# BACKPMAN30_CPU.net
KiCad netlist of a schematic drawn in Altium Designer
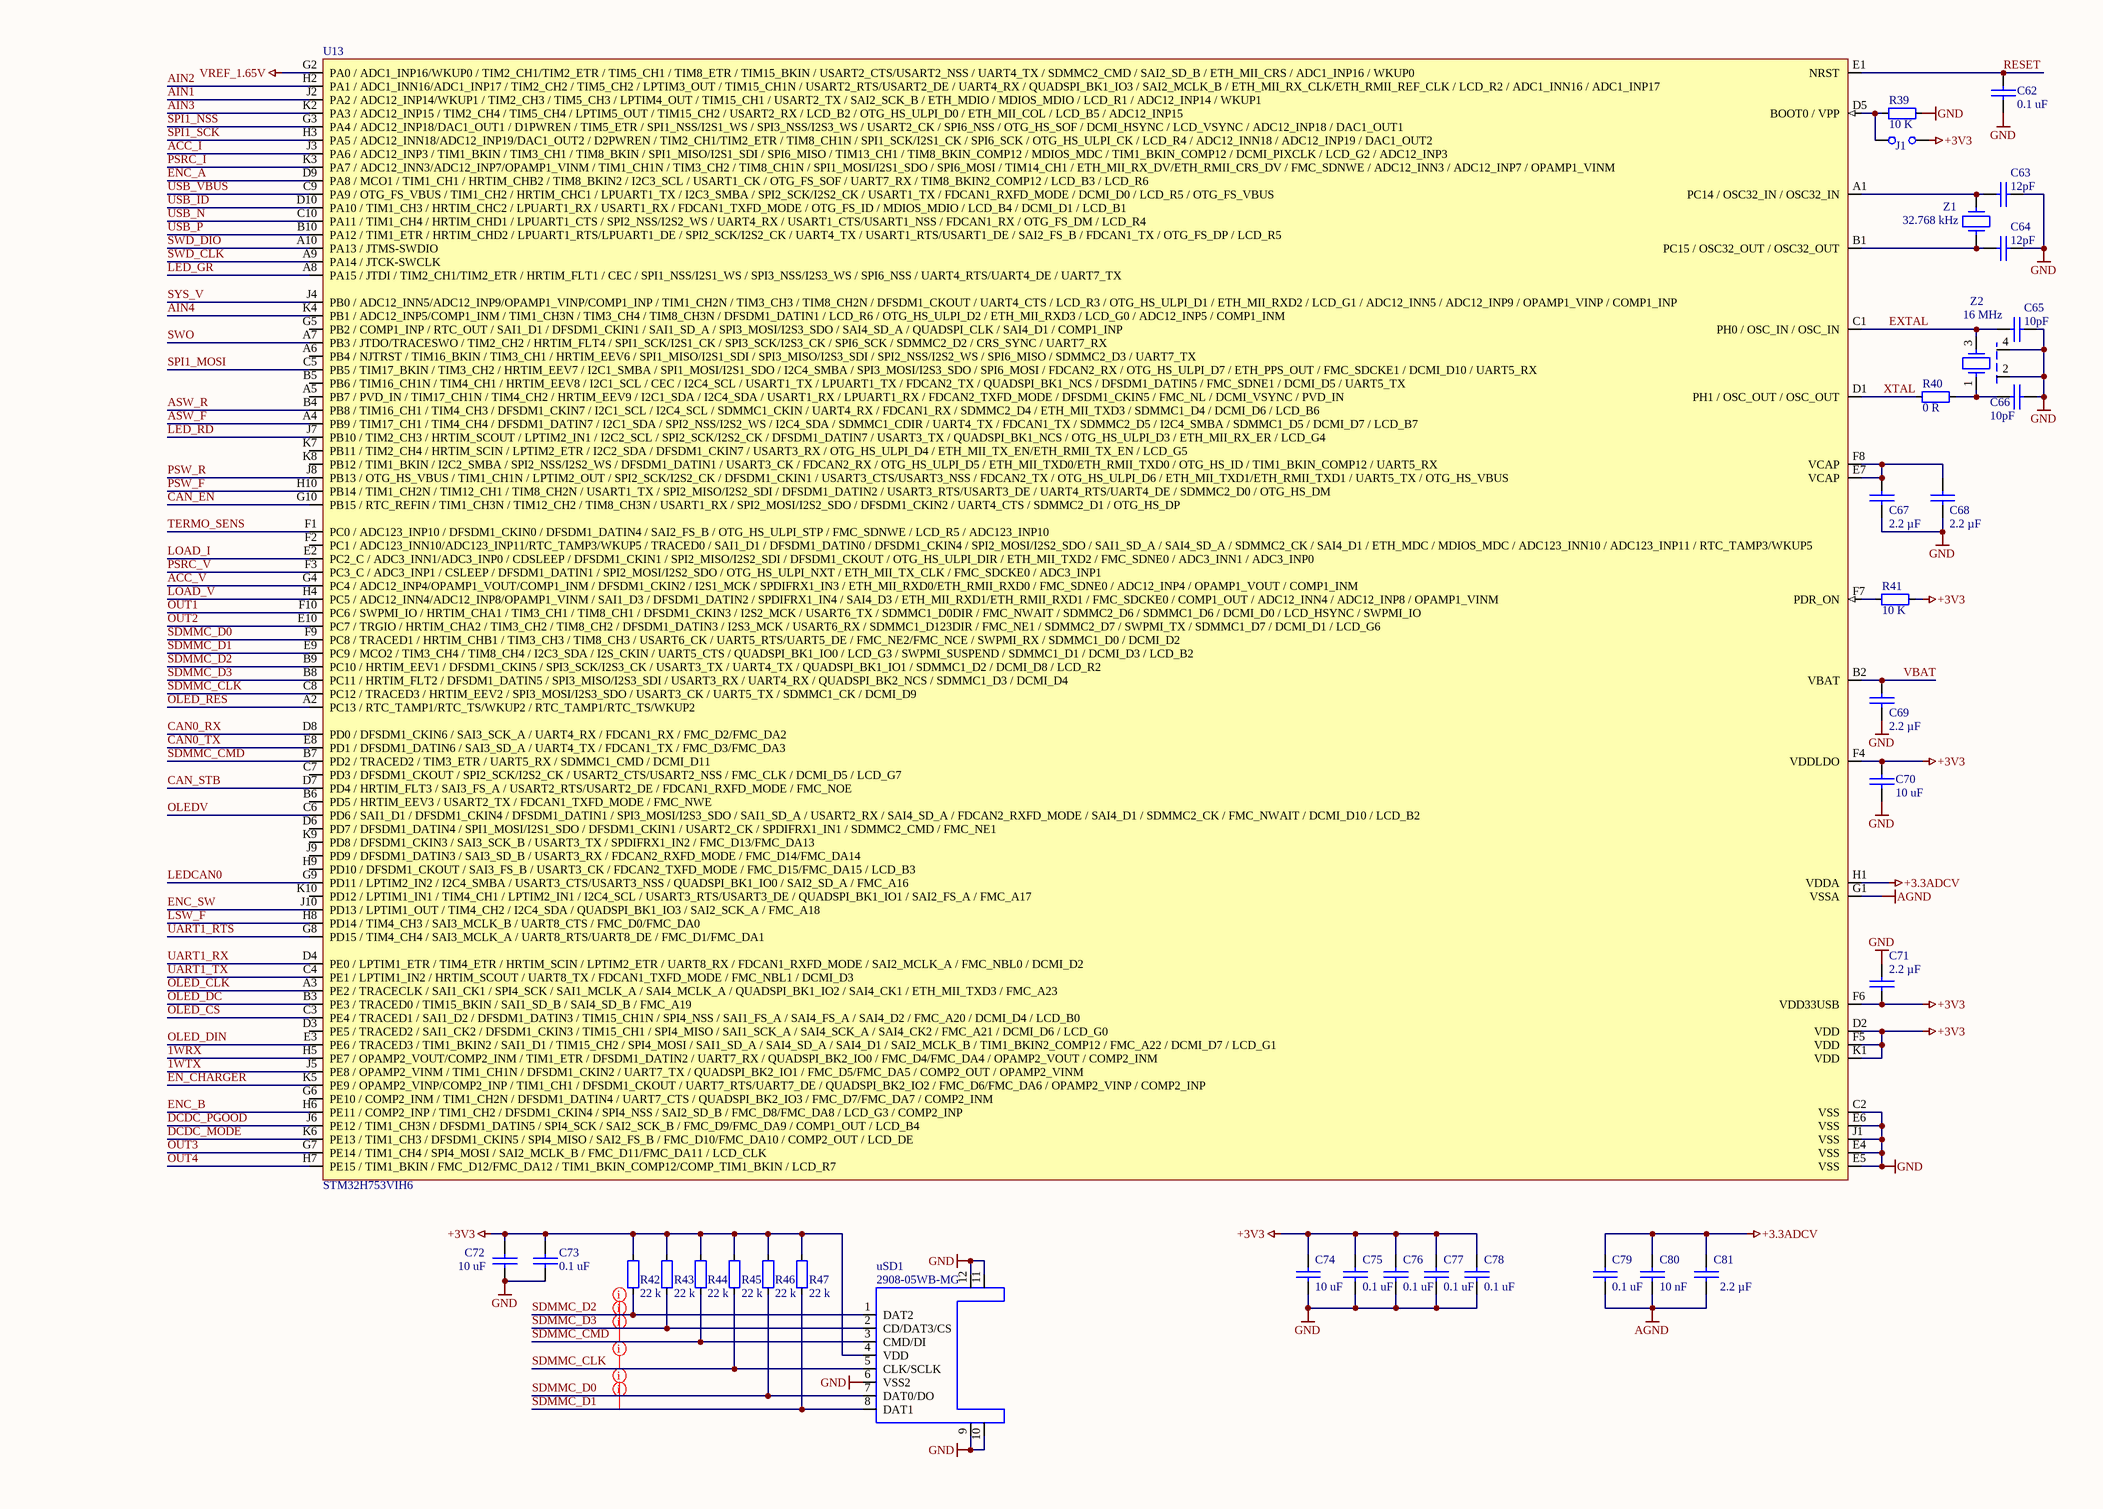
[diagram p0: BACKPMAN30_CPU.SchDoc]

(export (version "E")
  (design (tool "Eeschema 10.0.6"))
  (components
    (comp (ref "C62")
      (value "0.1 uF")
      (footprint "1608[0603]")
      (description "0.1 µF ±10% 50V Ceramic Capacitor X7R 0603 (1608 Metric), -55°C ~ 125°C")
      (fields
        (field (name "TOLERANCE") "+-10%")
        (field (name "MANUFACTURER") "Walsin Technology Corporation")
      )
      (libsource (lib "ea_Capacitors_0603") (part "0603B104K500CT"))
    )
    (comp (ref "C63")
      (value "12pF")
      (footprint "0402 CAP")
      (description "12pF, ±2%, 50V, C0G, NP0, 0402 (1005 Metric), -55°C ~ 125°C, -, General Purpose")
      (fields
        (field (name "PART NUMBER") "0402N120G500CT")
        (field (name "MANUFACTURER") "Walsin Technology Corporation")
      )
      (libsource (lib "ea_PassivComps") (part "Capacitor"))
    )
    (comp (ref "C64")
      (value "12pF")
      (footprint "0402 CAP")
      (description "12pF, ±2%, 50V, C0G, NP0, 0402 (1005 Metric), -55°C ~ 125°C, -, General Purpose")
      (fields
        (field (name "PART NUMBER") "0402N120G500CT")
        (field (name "MANUFACTURER") "Walsin Technology Corporation")
      )
      (libsource (lib "ea_PassivComps") (part "Capacitor"))
    )
    (comp (ref "C65")
      (value "10pF")
      (footprint "0402 CAP")
      (description "10pF, ±1%, 50V, C0G, NP0, 0402 (1005 Metric), -55°C ~ 125°C, -, Automotive")
      (fields
        (field (name "PART NUMBER") "GCM1555C1H100FA16D")
        (field (name "MANUFACTURER") "Murata Electronics North America")
      )
      (libsource (lib "ea_PassivComps") (part "Capacitor"))
    )
    (comp (ref "C66")
      (value "10pF")
      (footprint "0402 CAP")
      (description "10pF, ±1%, 50V, C0G, NP0, 0402 (1005 Metric), -55°C ~ 125°C, -, Automotive")
      (fields
        (field (name "PART NUMBER") "GCM1555C1H100FA16D")
        (field (name "MANUFACTURER") "Murata Electronics North America")
      )
      (libsource (lib "ea_PassivComps") (part "Capacitor"))
    )
    (comp (ref "C67")
      (value "2.2 µF")
      (footprint "1608[0603]")
      (description "2.2 µF ±10% 16V Ceramic Capacitor X5R 0603 (1608 Metric), -55°C ~ 85°C")
      (fields (field (name "MANUFACTURER") "TDK Corporation") (field (name "PARTNUM") "445-5157-1-ND"))
      (libsource (lib "ea_Capacitors_0603") (part "C1608X5R1C225K080AB"))
    )
    (comp (ref "C68")
      (value "2.2 µF")
      (footprint "1608[0603]")
      (description "2.2 µF ±10% 16V Ceramic Capacitor X5R 0603 (1608 Metric), -55°C ~ 85°C")
      (fields (field (name "MANUFACTURER") "TDK Corporation") (field (name "PARTNUM") "445-5157-1-ND"))
      (libsource (lib "ea_Capacitors_0603") (part "C1608X5R1C225K080AB"))
    )
    (comp (ref "C69")
      (value "2.2 µF")
      (footprint "1608[0603]")
      (description "2.2 µF ±10% 16V Ceramic Capacitor X5R 0603 (1608 Metric), -55°C ~ 85°C")
      (fields (field (name "MANUFACTURER") "TDK Corporation") (field (name "PARTNUM") "445-5157-1-ND"))
      (libsource (lib "ea_Capacitors_0603") (part "C1608X5R1C225K080AB"))
    )
    (comp (ref "C70")
      (value "10 uF")
      (footprint "2012[0805]")
      (description "10 µF ±10%, 25V, Ceramic Capacitor X5R 0805 (2012 Metric),  -55°C ~ 85°C")
      (fields (field (name "MANUFACTURER") "Murata Electronics") (field (name "TOLERANCE") "±10%"))
      (libsource (lib "ea_Capacitors_0805") (part "GRM21BR61E106KA73L"))
    )
    (comp (ref "C71")
      (value "2.2 µF")
      (footprint "1608[0603]")
      (description "2.2 µF ±10% 16V Ceramic Capacitor X5R 0603 (1608 Metric), -55°C ~ 85°C")
      (fields (field (name "MANUFACTURER") "TDK Corporation") (field (name "PARTNUM") "445-5157-1-ND"))
      (libsource (lib "ea_Capacitors_0603") (part "C1608X5R1C225K080AB"))
    )
    (comp (ref "C72")
      (value "10 uF")
      (footprint "2012[0805]")
      (description "10 µF ±10%, 25V, Ceramic Capacitor X5R 0805 (2012 Metric),  -55°C ~ 85°C")
      (fields (field (name "MANUFACTURER") "Murata Electronics") (field (name "PARTNUM") "490-5523-1-ND"))
      (libsource (lib "ea_Capacitors_0805") (part "GRM21BR61E106KA73L"))
    )
    (comp (ref "C73")
      (value "0.1 uF")
      (footprint "1608[0603]")
      (description "0.1 µF ±10% 50V Ceramic Capacitor X7R 0603 (1608 Metric), -55°C ~ 125°C")
      (fields
        (field (name "MANUFACTURER") "Walsin Technology Corporation")
        (field (name "PARTNUM") "1292-1643-1-ND")
      )
      (libsource (lib "ea_Capacitors_0603") (part "0603B104K500CT"))
    )
    (comp (ref "C74")
      (value "10 uF")
      (footprint "2012[0805]")
      (description "10 µF ±10%, 25V, Ceramic Capacitor X5R 0805 (2012 Metric),  -55°C ~ 85°C")
      (fields (field (name "MANUFACTURER") "Murata Electronics") (field (name "TOLERANCE") "±10%"))
      (libsource (lib "ea_Capacitors_0805") (part "GRM21BR61E106KA73L"))
    )
    (comp (ref "C75")
      (value "0.1 uF")
      (footprint "1608[0603]")
      (description "0.1 µF ±10% 50V Ceramic Capacitor X7R 0603 (1608 Metric), -55°C ~ 125°C")
      (fields
        (field (name "TOLERANCE") "+-10%")
        (field (name "MANUFACTURER") "Walsin Technology Corporation")
      )
      (libsource (lib "ea_Capacitors_0603") (part "0603B104K500CT"))
    )
    (comp (ref "C76")
      (value "0.1 uF")
      (footprint "1608[0603]")
      (description "0.1 µF ±10% 50V Ceramic Capacitor X7R 0603 (1608 Metric), -55°C ~ 125°C")
      (fields
        (field (name "TOLERANCE") "+-10%")
        (field (name "MANUFACTURER") "Walsin Technology Corporation")
      )
      (libsource (lib "ea_Capacitors_0603") (part "0603B104K500CT"))
    )
    (comp (ref "C77")
      (value "0.1 uF")
      (footprint "1608[0603]")
      (description "0.1 µF ±10% 50V Ceramic Capacitor X7R 0603 (1608 Metric), -55°C ~ 125°C")
      (fields
        (field (name "TOLERANCE") "+-10%")
        (field (name "MANUFACTURER") "Walsin Technology Corporation")
      )
      (libsource (lib "ea_Capacitors_0603") (part "0603B104K500CT"))
    )
    (comp (ref "C78")
      (value "0.1 uF")
      (footprint "1608[0603]")
      (description "0.1 µF ±10% 50V Ceramic Capacitor X7R 0603 (1608 Metric), -55°C ~ 125°C")
      (fields
        (field (name "TOLERANCE") "+-10%")
        (field (name "MANUFACTURER") "Walsin Technology Corporation")
      )
      (libsource (lib "ea_Capacitors_0603") (part "0603B104K500CT"))
    )
    (comp (ref "C79")
      (value "0.1 uF")
      (footprint "1608[0603]")
      (description "0.1 µF ±10% 50V Ceramic Capacitor X7R 0603 (1608 Metric), -55°C ~ 125°C")
      (fields
        (field (name "TOLERANCE") "+-10%")
        (field (name "MANUFACTURER") "Walsin Technology Corporation")
      )
      (libsource (lib "ea_Capacitors_0603") (part "0603B104K500CT"))
    )
    (comp (ref "C80")
      (value "10 nF")
      (footprint "1608[0603]")
      (description "10 nF, ±20%, 50V,  Ceramic Capacitor X7R 0603 (1608 Metric), -55°C ~ 125°C")
      (fields (field (name "TOLERANCE") "+-10%") (field (name "MANUFACTURER") "CAL-CHIP ELECTRONICS, INC."))
      (libsource (lib "ea_Capacitors_0603") (part "GMC10X7R103M50NT"))
    )
    (comp (ref "C81")
      (value "2.2 µF")
      (footprint "1608[0603]")
      (description "2.2 µF ±10% 16V Ceramic Capacitor X5R 0603 (1608 Metric), -55°C ~ 85°C")
      (fields (field (name "MANUFACTURER") "TDK Corporation") (field (name "PARTNUM") "445-5157-1-ND"))
      (libsource (lib "ea_Capacitors_0603") (part "C1608X5R1C225K080AB"))
    )
    (comp (ref "J1")
      (value "PH1-02-TA-HT")
      (footprint "HDR1X2V")
      (description "Connector Header Through Hole 2 position 0.100\" (2.54mm), Contact Length - Mating 6 mm")
      (fields (field (name "MANUFACTURER") "Adam Tech") (field (name "PARTNUM") "2057-PH1-02-UA-ND"))
      (libsource (lib "ea_Commutation") (part "PH1-02-UA"))
    )
    (comp (ref "R39")
      (value "10 K")
      (footprint "0603")
      (fields
        (field (name "MANUFACTURER") "Stackpole Electronics Inc")
        (field (name "TOLERANCE") "1%")
        (field (name "PARTNUM") "RMCF0603FT10K0CT-ND")
      )
      (libsource (lib "ea_Resistors_0603") (part "RMCF0603FT10K0"))
    )
    (comp (ref "R40")
      (value "0 R")
      (footprint "0603")
      (description "0 Ohms Jumper 0.1W, 1/10W Chip Resistor 0603 (1608 Metric) - Thick Film, -55°C ~ 155°C")
      (fields (field (name "MANUFACTURER") "Venkel") (field (name "VOLTAGE") "75 V"))
      (libsource (lib "ea_Resistors_0603") (part "CR0603-10W-000T"))
    )
    (comp (ref "R41")
      (value "10 K")
      (footprint "0603")
      (fields
        (field (name "MANUFACTURER") "Stackpole Electronics Inc")
        (field (name "TOLERANCE") "1%")
        (field (name "PARTNUM") "RMCF0603FT10K0CT-ND")
      )
      (libsource (lib "ea_Resistors_0603") (part "RMCF0603FT10K0"))
    )
    (comp (ref "R42")
      (value "22 k")
      (footprint "0402")
      (fields
        (field (name "MANUFACTURER") "Stackpole Electronics Inc")
        (field (name "TOLERANCE") "±1%")
        (field (name "VOLTAGE") "75V")
      )
      (libsource (lib "ea_PassivComps") (part "Resistor"))
    )
    (comp (ref "R43")
      (value "22 k")
      (footprint "0402")
      (fields
        (field (name "MANUFACTURER") "Stackpole Electronics Inc")
        (field (name "TOLERANCE") "±1%")
        (field (name "VOLTAGE") "75V")
      )
      (libsource (lib "ea_PassivComps") (part "Resistor"))
    )
    (comp (ref "R44")
      (value "22 k")
      (footprint "0402")
      (fields
        (field (name "MANUFACTURER") "Stackpole Electronics Inc")
        (field (name "TOLERANCE") "±1%")
        (field (name "VOLTAGE") "75V")
      )
      (libsource (lib "ea_PassivComps") (part "Resistor"))
    )
    (comp (ref "R45")
      (value "22 k")
      (footprint "0402")
      (fields
        (field (name "MANUFACTURER") "Stackpole Electronics Inc")
        (field (name "TOLERANCE") "±1%")
        (field (name "VOLTAGE") "75V")
      )
      (libsource (lib "ea_PassivComps") (part "Resistor"))
    )
    (comp (ref "R46")
      (value "22 k")
      (footprint "0402")
      (fields
        (field (name "MANUFACTURER") "Stackpole Electronics Inc")
        (field (name "TOLERANCE") "±1%")
        (field (name "VOLTAGE") "75V")
      )
      (libsource (lib "ea_PassivComps") (part "Resistor"))
    )
    (comp (ref "R47")
      (value "22 k")
      (footprint "0402")
      (fields
        (field (name "MANUFACTURER") "Stackpole Electronics Inc")
        (field (name "TOLERANCE") "±1%")
        (field (name "VOLTAGE") "75V")
      )
      (libsource (lib "ea_PassivComps") (part "Resistor"))
    )
    (comp (ref "U13")
      (value "STM32H753VIH6")
      (footprint "TFBGA100")
      (description "Cortex-M7, 480MHz 2MB FLASH, 1MB RAM, 100-TFBGA (8x8)")
      (fields (field (name "MANUFACTURER") "STMicroelectronics") (field (name "PARTNUM") "STM32H753VIH6-ND"))
      (libsource (lib "ea_IC_CPU") (part "STM32H753VIH6"))
    )
    (comp (ref "uSD1")
      (value "2908-05WB-MG")
      (footprint "2908-05WB-MG")
      (description "microSD cadr holder")
      (fields (field (name "MANUFACTURER") "3M"))
      (libsource (lib "ea_CARD_holders") (part "2908-05WB-MG"))
    )
    (comp (ref "Z1")
      (value "32.768 kHz")
      (footprint "ABS7")
      (description "32.768 kHz, 12.5 pF, 70 kOhm, ±20ppm, 3.2 x 1.5 mm, -40°C ~ 85°C")
      (fields (field (name "MANUFACTURER") "Abracon Corporation") (field (name "PARTNUM") "535-9542-1-ND"))
      (libsource (lib "ea_OSC_CLK_GEN") (part "ABS07-32.768KHZ-T"))
    )
    (comp (ref "Z2")
      (value "16 MHz")
      (footprint "4-SMD 2.00mm x 1.60mm")
      (description "16 MHz, 9 pF, ±10ppm, 2.00mm x 1.60mm, -20°C ~ 70°C")
      (fields (field (name "MANUFACTURER") "Abracon LLC") (field (name "PARTNUM") "535-13598-1-ND"))
      (libsource (lib "ea_OSC_CLK_GEN") (part "ABM11-16.000MHZ-9-B1U-T"))
    )
  )
  (nets
    (net (code "1") (name "+3.3ADCV") (class "Default")
      (node (ref "C79") (pin "2") (pinfunction "2_2") (pintype "passive"))
      (node (ref "C80") (pin "1") (pinfunction "1_1") (pintype "passive"))
      (node (ref "C81") (pin "1") (pinfunction "1_1") (pintype "passive"))
      (node (ref "U13") (pin "H1") (pinfunction "VDDA_H1") (pintype "power_in"))
    )
    (net (code "2") (name "+3V3") (class "Default")
      (node (ref "C70") (pin "2") (pinfunction "2_2") (pintype "passive"))
      (node (ref "C71") (pin "2") (pinfunction "2_2") (pintype "passive"))
      (node (ref "C72") (pin "2") (pinfunction "2_2") (pintype "passive"))
      (node (ref "C73") (pin "2") (pinfunction "2_2") (pintype "passive"))
      (node (ref "C74") (pin "2") (pinfunction "2_2") (pintype "passive"))
      (node (ref "C75") (pin "2") (pinfunction "2_2") (pintype "passive"))
      (node (ref "C76") (pin "2") (pinfunction "2_2") (pintype "passive"))
      (node (ref "C77") (pin "2") (pinfunction "2_2") (pintype "passive"))
      (node (ref "C78") (pin "2") (pinfunction "2_2") (pintype "passive"))
      (node (ref "J1") (pin "2") (pinfunction "2_2") (pintype "passive"))
      (node (ref "R41") (pin "1") (pinfunction "1_1") (pintype "passive"))
      (node (ref "R42") (pin "2") (pinfunction "2_2") (pintype "passive"))
      (node (ref "R43") (pin "2") (pinfunction "2_2") (pintype "passive"))
      (node (ref "R44") (pin "2") (pinfunction "2_2") (pintype "passive"))
      (node (ref "R45") (pin "2") (pinfunction "2_2") (pintype "passive"))
      (node (ref "R46") (pin "2") (pinfunction "2_2") (pintype "passive"))
      (node (ref "R47") (pin "2") (pinfunction "2_2") (pintype "passive"))
      (node (ref "U13") (pin "D2") (pinfunction "VDD_D2") (pintype "power_in"))
      (node (ref "U13") (pin "F4") (pinfunction "VDDLDO_F4") (pintype "power_in"))
      (node (ref "U13") (pin "F5") (pinfunction "VDD_F5") (pintype "power_in"))
      (node (ref "U13") (pin "F6") (pinfunction "VDD33USB_F6") (pintype "power_in"))
      (node (ref "U13") (pin "K1") (pinfunction "VDD_K1") (pintype "power_in"))
      (node (ref "uSD1") (pin "4") (pinfunction "VDD_4") (pintype "passive"))
    )
    (net (code "3") (name "/1WRX") (class "Default")
      (node (ref "U13") (pin "H5") (pinfunction "PE7_/_OPAMP2_VOUT/COMP2_INM_/_TIM1_ETR_/_DFSDM1_DATIN2_/_UART7_RX_/_QUADSPI_BK2_IO0_/_FMC_D4/FMC_DA4_/_OPAMP2_VOUT_/_COMP2_INM_H5") (pintype "bidirectional"))
    )
    (net (code "4") (name "/1WTX") (class "Default")
      (node (ref "U13") (pin "J5") (pinfunction "PE8_/_OPAMP2_VINM_/_TIM1_CH1N_/_DFSDM1_CKIN2_/_UART7_TX_/_QUADSPI_BK2_IO1_/_FMC_D5/FMC_DA5_/_COMP2_OUT_/_OPAMP2_VINM_J5") (pintype "bidirectional"))
    )
    (net (code "5") (name "/ACC_I") (class "Default")
      (node (ref "U13") (pin "J3") (pinfunction "PA6_/_ADC12_INP3_/_TIM1_BKIN_/_TIM3_CH1_/_TIM8_BKIN_/_SPI1_MISO/I2S1_SDI_/_SPI6_MISO_/_TIM13_CH1_/_TIM8_BKIN_COMP12_/_MDIOS_MDC_/_TIM1_BKIN_COMP12_/_DCMI_PIXCLK_/_LCD_G2_/_ADC12_INP3_J3") (pintype "bidirectional"))
    )
    (net (code "6") (name "/ACC_V") (class "Default")
      (node (ref "U13") (pin "G4") (pinfunction "PC4_/_ADC12_INP4/OPAMP1_VOUT/COMP1_INM_/_DFSDM1_CKIN2_/_I2S1_MCK_/_SPDIFRX1_IN3_/_ETH_MII_RXD0/ETH_RMII_RXD0_/_FMC_SDNE0_/_ADC12_INP4_/_OPAMP1_VOUT_/_COMP1_INM_G4") (pintype "bidirectional"))
    )
    (net (code "7") (name "/AIN1") (class "Default")
      (node (ref "U13") (pin "J2") (pinfunction "PA2_/_ADC12_INP14/WKUP1_/_TIM2_CH3_/_TIM5_CH3_/_LPTIM4_OUT_/_TIM15_CH1_/_USART2_TX_/_SAI2_SCK_B_/_ETH_MDIO_/_MDIOS_MDIO_/_LCD_R1_/_ADC12_INP14_/_WKUP1_J2") (pintype "bidirectional"))
    )
    (net (code "8") (name "/AIN2") (class "Default")
      (node (ref "U13") (pin "H2") (pinfunction "PA1_/_ADC1_INN16/ADC1_INP17_/_TIM2_CH2_/_TIM5_CH2_/_LPTIM3_OUT_/_TIM15_CH1N_/_USART2_RTS/USART2_DE_/_UART4_RX_/_QUADSPI_BK1_IO3_/_SAI2_MCLK_B_/_ETH_MII_RX_CLK/ETH_RMII_REF_CLK_/_LCD_R2_/_ADC1_INN16_/_ADC1_INP17_H2") (pintype "bidirectional"))
    )
    (net (code "9") (name "/AIN3") (class "Default")
      (node (ref "U13") (pin "K2") (pinfunction "PA3_/_ADC12_INP15_/_TIM2_CH4_/_TIM5_CH4_/_LPTIM5_OUT_/_TIM15_CH2_/_USART2_RX_/_LCD_B2_/_OTG_HS_ULPI_D0_/_ETH_MII_COL_/_LCD_B5_/_ADC12_INP15_K2") (pintype "bidirectional"))
    )
    (net (code "10") (name "/AIN4") (class "Default")
      (node (ref "U13") (pin "K4") (pinfunction "PB1_/_ADC12_INP5/COMP1_INM_/_TIM1_CH3N_/_TIM3_CH4_/_TIM8_CH3N_/_DFSDM1_DATIN1_/_LCD_R6_/_OTG_HS_ULPI_D2_/_ETH_MII_RXD3_/_LCD_G0_/_ADC12_INP5_/_COMP1_INM_K4") (pintype "bidirectional"))
    )
    (net (code "11") (name "/ASW_F") (class "Default")
      (node (ref "U13") (pin "A4") (pinfunction "PB9_/_TIM17_CH1_/_TIM4_CH4_/_DFSDM1_DATIN7_/_I2C1_SDA_/_SPI2_NSS/I2S2_WS_/_I2C4_SDA_/_SDMMC1_CDIR_/_UART4_TX_/_FDCAN1_TX_/_SDMMC2_D5_/_I2C4_SMBA_/_SDMMC1_D5_/_DCMI_D7_/_LCD_B7_A4") (pintype "bidirectional"))
    )
    (net (code "12") (name "/ASW_R") (class "Default")
      (node (ref "U13") (pin "B4") (pinfunction "PB8_/_TIM16_CH1_/_TIM4_CH3_/_DFSDM1_CKIN7_/_I2C1_SCL_/_I2C4_SCL_/_SDMMC1_CKIN_/_UART4_RX_/_FDCAN1_RX_/_SDMMC2_D4_/_ETH_MII_TXD3_/_SDMMC1_D4_/_DCMI_D6_/_LCD_B6_B4") (pintype "bidirectional"))
    )
    (net (code "13") (name "/CAN0_RX") (class "Default")
      (node (ref "U13") (pin "D8") (pinfunction "PD0_/_DFSDM1_CKIN6_/_SAI3_SCK_A_/_UART4_RX_/_FDCAN1_RX_/_FMC_D2/FMC_DA2_D8") (pintype "bidirectional"))
    )
    (net (code "14") (name "/CAN0_TX") (class "Default")
      (node (ref "U13") (pin "E8") (pinfunction "PD1_/_DFSDM1_DATIN6_/_SAI3_SD_A_/_UART4_TX_/_FDCAN1_TX_/_FMC_D3/FMC_DA3_E8") (pintype "bidirectional"))
    )
    (net (code "15") (name "/CAN_EN") (class "Default")
      (node (ref "U13") (pin "G10") (pinfunction "PB15_/_RTC_REFIN_/_TIM1_CH3N_/_TIM12_CH2_/_TIM8_CH3N_/_USART1_RX_/_SPI2_MOSI/I2S2_SDO_/_DFSDM1_CKIN2_/_UART4_CTS_/_SDMMC2_D1_/_OTG_HS_DP_G10") (pintype "bidirectional"))
    )
    (net (code "16") (name "/CAN_STB") (class "Default")
      (node (ref "U13") (pin "D7") (pinfunction "PD4_/_HRTIM_FLT3_/_SAI3_FS_A_/_USART2_RTS/USART2_DE_/_FDCAN1_RXFD_MODE_/_FMC_NOE_D7") (pintype "bidirectional"))
    )
    (net (code "17") (name "/DCDC_MODE") (class "Default")
      (node (ref "U13") (pin "K6") (pinfunction "PE13_/_TIM1_CH3_/_DFSDM1_CKIN5_/_SPI4_MISO_/_SAI2_FS_B_/_FMC_D10/FMC_DA10_/_COMP2_OUT_/_LCD_DE_K6") (pintype "bidirectional"))
    )
    (net (code "18") (name "/DCDC_PGOOD") (class "Default")
      (node (ref "U13") (pin "J6") (pinfunction "PE12_/_TIM1_CH3N_/_DFSDM1_DATIN5_/_SPI4_SCK_/_SAI2_SCK_B_/_FMC_D9/FMC_DA9_/_COMP1_OUT_/_LCD_B4_J6") (pintype "bidirectional"))
    )
    (net (code "19") (name "/ENC_A") (class "Default")
      (node (ref "U13") (pin "D9") (pinfunction "PA8_/_MCO1_/_TIM1_CH1_/_HRTIM_CHB2_/_TIM8_BKIN2_/_I2C3_SCL_/_USART1_CK_/_OTG_FS_SOF_/_UART7_RX_/_TIM8_BKIN2_COMP12_/_LCD_B3_/_LCD_R6_D9") (pintype "bidirectional"))
    )
    (net (code "20") (name "/ENC_B") (class "Default")
      (node (ref "U13") (pin "H6") (pinfunction "PE11_/_COMP2_INP_/_TIM1_CH2_/_DFSDM1_CKIN4_/_SPI4_NSS_/_SAI2_SD_B_/_FMC_D8/FMC_DA8_/_LCD_G3_/_COMP2_INP_H6") (pintype "bidirectional"))
    )
    (net (code "21") (name "/ENC_SW") (class "Default")
      (node (ref "U13") (pin "J10") (pinfunction "PD13_/_LPTIM1_OUT_/_TIM4_CH2_/_I2C4_SDA_/_QUADSPI_BK1_IO3_/_SAI2_SCK_A_/_FMC_A18_J10") (pintype "bidirectional"))
    )
    (net (code "22") (name "/EN_CHARGER") (class "Default")
      (node (ref "U13") (pin "K5") (pinfunction "PE9_/_OPAMP2_VINP/COMP2_INP_/_TIM1_CH1_/_DFSDM1_CKOUT_/_UART7_RTS/UART7_DE_/_QUADSPI_BK2_IO2_/_FMC_D6/FMC_DA6_/_OPAMP2_VINP_/_COMP2_INP_K5") (pintype "bidirectional"))
    )
    (net (code "23") (name "/EXTAL") (class "Default")
      (node (ref "C65") (pin "1") (pinfunction "1_1") (pintype "passive"))
      (node (ref "U13") (pin "C1") (pinfunction "PH0_/_OSC_IN_/_OSC_IN_C1") (pintype "bidirectional"))
      (node (ref "Z2") (pin "3") (pinfunction "3_3") (pintype "passive"))
    )
    (net (code "24") (name "/LEDCAN0") (class "Default")
      (node (ref "U13") (pin "G9") (pinfunction "PD11_/_LPTIM2_IN2_/_I2C4_SMBA_/_USART3_CTS/USART3_NSS_/_QUADSPI_BK1_IO0_/_SAI2_SD_A_/_FMC_A16_G9") (pintype "bidirectional"))
    )
    (net (code "25") (name "/LED_GR") (class "Default")
      (node (ref "U13") (pin "A8") (pinfunction "PA15_/_JTDI_/_TIM2_CH1/TIM2_ETR_/_HRTIM_FLT1_/_CEC_/_SPI1_NSS/I2S1_WS_/_SPI3_NSS/I2S3_WS_/_SPI6_NSS_/_UART4_RTS/UART4_DE_/_UART7_TX_A8") (pintype "bidirectional"))
    )
    (net (code "26") (name "/LED_RD") (class "Default")
      (node (ref "U13") (pin "J7") (pinfunction "PB10_/_TIM2_CH3_/_HRTIM_SCOUT_/_LPTIM2_IN1_/_I2C2_SCL_/_SPI2_SCK/I2S2_CK_/_DFSDM1_DATIN7_/_USART3_TX_/_QUADSPI_BK1_NCS_/_OTG_HS_ULPI_D3_/_ETH_MII_RX_ER_/_LCD_G4_J7") (pintype "bidirectional"))
    )
    (net (code "27") (name "/LOAD_I") (class "Default")
      (node (ref "U13") (pin "E2") (pinfunction "PC2_C_/_ADC3_INN1/ADC3_INP0_/_CDSLEEP_/_DFSDM1_CKIN1_/_SPI2_MISO/I2S2_SDI_/_DFSDM1_CKOUT_/_OTG_HS_ULPI_DIR_/_ETH_MII_TXD2_/_FMC_SDNE0_/_ADC3_INN1_/_ADC3_INP0_E2") (pintype "bidirectional"))
    )
    (net (code "28") (name "/LOAD_V") (class "Default")
      (node (ref "U13") (pin "H4") (pinfunction "PC5_/_ADC12_INN4/ADC12_INP8/OPAMP1_VINM_/_SAI1_D3_/_DFSDM1_DATIN2_/_SPDIFRX1_IN4_/_SAI4_D3_/_ETH_MII_RXD1/ETH_RMII_RXD1_/_FMC_SDCKE0_/_COMP1_OUT_/_ADC12_INN4_/_ADC12_INP8_/_OPAMP1_VINM_H4") (pintype "bidirectional"))
    )
    (net (code "29") (name "/LSW_F") (class "Default")
      (node (ref "U13") (pin "H8") (pinfunction "PD14_/_TIM4_CH3_/_SAI3_MCLK_B_/_UART8_CTS_/_FMC_D0/FMC_DA0_H8") (pintype "bidirectional"))
    )
    (net (code "30") (name "/OLEDV") (class "Default")
      (node (ref "U13") (pin "C6") (pinfunction "PD6_/_SAI1_D1_/_DFSDM1_CKIN4_/_DFSDM1_DATIN1_/_SPI3_MOSI/I2S3_SDO_/_SAI1_SD_A_/_USART2_RX_/_SAI4_SD_A_/_FDCAN2_RXFD_MODE_/_SAI4_D1_/_SDMMC2_CK_/_FMC_NWAIT_/_DCMI_D10_/_LCD_B2_C6") (pintype "bidirectional"))
    )
    (net (code "31") (name "/OLED_CLK") (class "Default")
      (node (ref "U13") (pin "A3") (pinfunction "PE2_/_TRACECLK_/_SAI1_CK1_/_SPI4_SCK_/_SAI1_MCLK_A_/_SAI4_MCLK_A_/_QUADSPI_BK1_IO2_/_SAI4_CK1_/_ETH_MII_TXD3_/_FMC_A23_A3") (pintype "bidirectional"))
    )
    (net (code "32") (name "/OLED_CS") (class "Default")
      (node (ref "U13") (pin "C3") (pinfunction "PE4_/_TRACED1_/_SAI1_D2_/_DFSDM1_DATIN3_/_TIM15_CH1N_/_SPI4_NSS_/_SAI1_FS_A_/_SAI4_FS_A_/_SAI4_D2_/_FMC_A20_/_DCMI_D4_/_LCD_B0_C3") (pintype "bidirectional"))
    )
    (net (code "33") (name "/OLED_DC") (class "Default")
      (node (ref "U13") (pin "B3") (pinfunction "PE3_/_TRACED0_/_TIM15_BKIN_/_SAI1_SD_B_/_SAI4_SD_B_/_FMC_A19_B3") (pintype "bidirectional"))
    )
    (net (code "34") (name "/OLED_DIN") (class "Default")
      (node (ref "U13") (pin "E3") (pinfunction "PE6_/_TRACED3_/_TIM1_BKIN2_/_SAI1_D1_/_TIM15_CH2_/_SPI4_MOSI_/_SAI1_SD_A_/_SAI4_SD_A_/_SAI4_D1_/_SAI2_MCLK_B_/_TIM1_BKIN2_COMP12_/_FMC_A22_/_DCMI_D7_/_LCD_G1_E3") (pintype "bidirectional"))
    )
    (net (code "35") (name "/OLED_RES") (class "Default")
      (node (ref "U13") (pin "A2") (pinfunction "PC13_/_RTC_TAMP1/RTC_TS/WKUP2_/_RTC_TAMP1/RTC_TS/WKUP2_A2") (pintype "bidirectional"))
    )
    (net (code "36") (name "/OUT1") (class "Default")
      (node (ref "U13") (pin "F10") (pinfunction "PC6_/_SWPMI_IO_/_HRTIM_CHA1_/_TIM3_CH1_/_TIM8_CH1_/_DFSDM1_CKIN3_/_I2S2_MCK_/_USART6_TX_/_SDMMC1_D0DIR_/_FMC_NWAIT_/_SDMMC2_D6_/_SDMMC1_D6_/_DCMI_D0_/_LCD_HSYNC_/_SWPMI_IO_F10") (pintype "bidirectional"))
    )
    (net (code "37") (name "/OUT2") (class "Default")
      (node (ref "U13") (pin "E10") (pinfunction "PC7_/_TRGIO_/_HRTIM_CHA2_/_TIM3_CH2_/_TIM8_CH2_/_DFSDM1_DATIN3_/_I2S3_MCK_/_USART6_RX_/_SDMMC1_D123DIR_/_FMC_NE1_/_SDMMC2_D7_/_SWPMI_TX_/_SDMMC1_D7_/_DCMI_D1_/_LCD_G6_E10") (pintype "bidirectional"))
    )
    (net (code "38") (name "/OUT3") (class "Default")
      (node (ref "U13") (pin "G7") (pinfunction "PE14_/_TIM1_CH4_/_SPI4_MOSI_/_SAI2_MCLK_B_/_FMC_D11/FMC_DA11_/_LCD_CLK_G7") (pintype "bidirectional"))
    )
    (net (code "39") (name "/OUT4") (class "Default")
      (node (ref "U13") (pin "H7") (pinfunction "PE15_/_TIM1_BKIN_/_FMC_D12/FMC_DA12_/_TIM1_BKIN_COMP12/COMP_TIM1_BKIN_/_LCD_R7_H7") (pintype "bidirectional"))
    )
    (net (code "40") (name "/PSRC_I") (class "Default")
      (node (ref "U13") (pin "K3") (pinfunction "PA7_/_ADC12_INN3/ADC12_INP7/OPAMP1_VINM_/_TIM1_CH1N_/_TIM3_CH2_/_TIM8_CH1N_/_SPI1_MOSI/I2S1_SDO_/_SPI6_MOSI_/_TIM14_CH1_/_ETH_MII_RX_DV/ETH_RMII_CRS_DV_/_FMC_SDNWE_/_ADC12_INN3_/_ADC12_INP7_/_OPAMP1_VINM_K3") (pintype "bidirectional"))
    )
    (net (code "41") (name "/PSRC_V") (class "Default")
      (node (ref "U13") (pin "F3") (pinfunction "PC3_C_/_ADC3_INP1_/_CSLEEP_/_DFSDM1_DATIN1_/_SPI2_MOSI/I2S2_SDO_/_OTG_HS_ULPI_NXT_/_ETH_MII_TX_CLK_/_FMC_SDCKE0_/_ADC3_INP1_F3") (pintype "bidirectional"))
    )
    (net (code "42") (name "/PSW_F") (class "Default")
      (node (ref "U13") (pin "H10") (pinfunction "PB14_/_TIM1_CH2N_/_TIM12_CH1_/_TIM8_CH2N_/_USART1_TX_/_SPI2_MISO/I2S2_SDI_/_DFSDM1_DATIN2_/_USART3_RTS/USART3_DE_/_UART4_RTS/UART4_DE_/_SDMMC2_D0_/_OTG_HS_DM_H10") (pintype "bidirectional"))
    )
    (net (code "43") (name "/PSW_R") (class "Default")
      (node (ref "U13") (pin "J8") (pinfunction "PB13_/_OTG_HS_VBUS_/_TIM1_CH1N_/_LPTIM2_OUT_/_SPI2_SCK/I2S2_CK_/_DFSDM1_CKIN1_/_USART3_CTS/USART3_NSS_/_FDCAN2_TX_/_OTG_HS_ULPI_D6_/_ETH_MII_TXD1/ETH_RMII_TXD1_/_UART5_TX_/_OTG_HS_VBUS_J8") (pintype "bidirectional"))
    )
    (net (code "44") (name "/RESET") (class "Default")
      (node (ref "C62") (pin "1") (pinfunction "1_1") (pintype "passive"))
      (node (ref "U13") (pin "E1") (pinfunction "NRST_E1") (pintype "bidirectional"))
    )
    (net (code "45") (name "/SDMMC_CLK") (class "Default")
      (node (ref "R45") (pin "1") (pinfunction "1_1") (pintype "passive"))
      (node (ref "U13") (pin "C8") (pinfunction "PC12_/_TRACED3_/_HRTIM_EEV2_/_SPI3_MOSI/I2S3_SDO_/_USART3_CK_/_UART5_TX_/_SDMMC1_CK_/_DCMI_D9_C8") (pintype "bidirectional"))
      (node (ref "uSD1") (pin "5") (pinfunction "CLK/SCLK_5") (pintype "passive"))
    )
    (net (code "46") (name "/SDMMC_CMD") (class "Default")
      (node (ref "R44") (pin "1") (pinfunction "1_1") (pintype "passive"))
      (node (ref "U13") (pin "B7") (pinfunction "PD2_/_TRACED2_/_TIM3_ETR_/_UART5_RX_/_SDMMC1_CMD_/_DCMI_D11_B7") (pintype "bidirectional"))
      (node (ref "uSD1") (pin "3") (pinfunction "CMD/DI_3") (pintype "passive"))
    )
    (net (code "47") (name "/SDMMC_D0") (class "Default")
      (node (ref "R46") (pin "1") (pinfunction "1_1") (pintype "passive"))
      (node (ref "U13") (pin "F9") (pinfunction "PC8_/_TRACED1_/_HRTIM_CHB1_/_TIM3_CH3_/_TIM8_CH3_/_USART6_CK_/_UART5_RTS/UART5_DE_/_FMC_NE2/FMC_NCE_/_SWPMI_RX_/_SDMMC1_D0_/_DCMI_D2_F9") (pintype "bidirectional"))
      (node (ref "uSD1") (pin "7") (pinfunction "DAT0/DO_7") (pintype "passive"))
    )
    (net (code "48") (name "/SDMMC_D1") (class "Default")
      (node (ref "R47") (pin "1") (pinfunction "1_1") (pintype "passive"))
      (node (ref "U13") (pin "E9") (pinfunction "PC9_/_MCO2_/_TIM3_CH4_/_TIM8_CH4_/_I2C3_SDA_/_I2S_CKIN_/_UART5_CTS_/_QUADSPI_BK1_IO0_/_LCD_G3_/_SWPMI_SUSPEND_/_SDMMC1_D1_/_DCMI_D3_/_LCD_B2_E9") (pintype "bidirectional"))
      (node (ref "uSD1") (pin "8") (pinfunction "DAT1_8") (pintype "passive"))
    )
    (net (code "49") (name "/SDMMC_D2") (class "Default")
      (node (ref "R42") (pin "1") (pinfunction "1_1") (pintype "passive"))
      (node (ref "U13") (pin "B9") (pinfunction "PC10_/_HRTIM_EEV1_/_DFSDM1_CKIN5_/_SPI3_SCK/I2S3_CK_/_USART3_TX_/_UART4_TX_/_QUADSPI_BK1_IO1_/_SDMMC1_D2_/_DCMI_D8_/_LCD_R2_B9") (pintype "bidirectional"))
      (node (ref "uSD1") (pin "1") (pinfunction "DAT2_1") (pintype "passive"))
    )
    (net (code "50") (name "/SDMMC_D3") (class "Default")
      (node (ref "R43") (pin "1") (pinfunction "1_1") (pintype "passive"))
      (node (ref "U13") (pin "B8") (pinfunction "PC11_/_HRTIM_FLT2_/_DFSDM1_DATIN5_/_SPI3_MISO/I2S3_SDI_/_USART3_RX_/_UART4_RX_/_QUADSPI_BK2_NCS_/_SDMMC1_D3_/_DCMI_D4_B8") (pintype "bidirectional"))
      (node (ref "uSD1") (pin "2") (pinfunction "CD/DAT3/CS_2") (pintype "passive"))
    )
    (net (code "51") (name "/SPI1_MOSI") (class "Default")
      (node (ref "U13") (pin "C5") (pinfunction "PB5_/_TIM17_BKIN_/_TIM3_CH2_/_HRTIM_EEV7_/_I2C1_SMBA_/_SPI1_MOSI/I2S1_SDO_/_I2C4_SMBA_/_SPI3_MOSI/I2S3_SDO_/_SPI6_MOSI_/_FDCAN2_RX_/_OTG_HS_ULPI_D7_/_ETH_PPS_OUT_/_FMC_SDCKE1_/_DCMI_D10_/_UART5_RX_C5") (pintype "bidirectional"))
    )
    (net (code "52") (name "/SPI1_NSS") (class "Default")
      (node (ref "U13") (pin "G3") (pinfunction "PA4_/_ADC12_INP18/DAC1_OUT1_/_D1PWREN_/_TIM5_ETR_/_SPI1_NSS/I2S1_WS_/_SPI3_NSS/I2S3_WS_/_USART2_CK_/_SPI6_NSS_/_OTG_HS_SOF_/_DCMI_HSYNC_/_LCD_VSYNC_/_ADC12_INP18_/_DAC1_OUT1_G3") (pintype "bidirectional"))
    )
    (net (code "53") (name "/SPI1_SCK") (class "Default")
      (node (ref "U13") (pin "H3") (pinfunction "PA5_/_ADC12_INN18/ADC12_INP19/DAC1_OUT2_/_D2PWREN_/_TIM2_CH1/TIM2_ETR_/_TIM8_CH1N_/_SPI1_SCK/I2S1_CK_/_SPI6_SCK_/_OTG_HS_ULPI_CK_/_LCD_R4_/_ADC12_INN18_/_ADC12_INP19_/_DAC1_OUT2_H3") (pintype "bidirectional"))
    )
    (net (code "54") (name "/SWD_CLK") (class "Default")
      (node (ref "U13") (pin "A9") (pinfunction "PA14_/_JTCK-SWCLK_A9") (pintype "bidirectional"))
    )
    (net (code "55") (name "/SWD_DIO") (class "Default")
      (node (ref "U13") (pin "A10") (pinfunction "PA13_/_JTMS-SWDIO_A10") (pintype "bidirectional"))
    )
    (net (code "56") (name "/SWO") (class "Default")
      (node (ref "U13") (pin "A7") (pinfunction "PB3_/_JTDO/TRACESWO_/_TIM2_CH2_/_HRTIM_FLT4_/_SPI1_SCK/I2S1_CK_/_SPI3_SCK/I2S3_CK_/_SPI6_SCK_/_SDMMC2_D2_/_CRS_SYNC_/_UART7_RX_A7") (pintype "bidirectional"))
    )
    (net (code "57") (name "/SYS_V") (class "Default")
      (node (ref "U13") (pin "J4") (pinfunction "PB0_/_ADC12_INN5/ADC12_INP9/OPAMP1_VINP/COMP1_INP_/_TIM1_CH2N_/_TIM3_CH3_/_TIM8_CH2N_/_DFSDM1_CKOUT_/_UART4_CTS_/_LCD_R3_/_OTG_HS_ULPI_D1_/_ETH_MII_RXD2_/_LCD_G1_/_ADC12_INN5_/_ADC12_INP9_/_OPAMP1_VINP_/_COMP1_INP_J4") (pintype "bidirectional"))
    )
    (net (code "58") (name "/TERMO_SENS") (class "Default")
      (node (ref "U13") (pin "F1") (pinfunction "PC0_/_ADC123_INP10_/_DFSDM1_CKIN0_/_DFSDM1_DATIN4_/_SAI2_FS_B_/_OTG_HS_ULPI_STP_/_FMC_SDNWE_/_LCD_R5_/_ADC123_INP10_F1") (pintype "bidirectional"))
    )
    (net (code "59") (name "/UART1_RTS") (class "Default")
      (node (ref "U13") (pin "G8") (pinfunction "PD15_/_TIM4_CH4_/_SAI3_MCLK_A_/_UART8_RTS/UART8_DE_/_FMC_D1/FMC_DA1_G8") (pintype "bidirectional"))
    )
    (net (code "60") (name "/UART1_RX") (class "Default")
      (node (ref "U13") (pin "D4") (pinfunction "PE0_/_LPTIM1_ETR_/_TIM4_ETR_/_HRTIM_SCIN_/_LPTIM2_ETR_/_UART8_RX_/_FDCAN1_RXFD_MODE_/_SAI2_MCLK_A_/_FMC_NBL0_/_DCMI_D2_D4") (pintype "bidirectional"))
    )
    (net (code "61") (name "/UART1_TX") (class "Default")
      (node (ref "U13") (pin "C4") (pinfunction "PE1_/_LPTIM1_IN2_/_HRTIM_SCOUT_/_UART8_TX_/_FDCAN1_TXFD_MODE_/_FMC_NBL1_/_DCMI_D3_C4") (pintype "bidirectional"))
    )
    (net (code "62") (name "/USB_ID") (class "Default")
      (node (ref "U13") (pin "D10") (pinfunction "PA10_/_TIM1_CH3_/_HRTIM_CHC2_/_LPUART1_RX_/_USART1_RX_/_FDCAN1_TXFD_MODE_/_OTG_FS_ID_/_MDIOS_MDIO_/_LCD_B4_/_DCMI_D1_/_LCD_B1_D10") (pintype "bidirectional"))
    )
    (net (code "63") (name "/USB_N") (class "Default")
      (node (ref "U13") (pin "C10") (pinfunction "PA11_/_TIM1_CH4_/_HRTIM_CHD1_/_LPUART1_CTS_/_SPI2_NSS/I2S2_WS_/_UART4_RX_/_USART1_CTS/USART1_NSS_/_FDCAN1_RX_/_OTG_FS_DM_/_LCD_R4_C10") (pintype "bidirectional"))
    )
    (net (code "64") (name "/USB_P") (class "Default")
      (node (ref "U13") (pin "B10") (pinfunction "PA12_/_TIM1_ETR_/_HRTIM_CHD2_/_LPUART1_RTS/LPUART1_DE_/_SPI2_SCK/I2S2_CK_/_UART4_TX_/_USART1_RTS/USART1_DE_/_SAI2_FS_B_/_FDCAN1_TX_/_OTG_FS_DP_/_LCD_R5_B10") (pintype "bidirectional"))
    )
    (net (code "65") (name "/USB_VBUS") (class "Default")
      (node (ref "U13") (pin "C9") (pinfunction "PA9_/_OTG_FS_VBUS_/_TIM1_CH2_/_HRTIM_CHC1_/_LPUART1_TX_/_I2C3_SMBA_/_SPI2_SCK/I2S2_CK_/_USART1_TX_/_FDCAN1_RXFD_MODE_/_DCMI_D0_/_LCD_R5_/_OTG_FS_VBUS_C9") (pintype "bidirectional"))
    )
    (net (code "66") (name "/VBAT") (class "Default")
      (node (ref "C69") (pin "1") (pinfunction "1_1") (pintype "passive"))
      (node (ref "U13") (pin "B2") (pinfunction "VBAT_B2") (pintype "power_in"))
    )
    (net (code "67") (name "/XTAL") (class "Default")
      (node (ref "R40") (pin "2") (pinfunction "2_2") (pintype "passive"))
      (node (ref "U13") (pin "D1") (pinfunction "PH1_/_OSC_OUT_/_OSC_OUT_D1") (pintype "bidirectional"))
    )
    (net (code "68") (name "AGND") (class "Default")
      (node (ref "C79") (pin "1") (pinfunction "1_1") (pintype "passive"))
      (node (ref "C80") (pin "2") (pinfunction "2_2") (pintype "passive"))
      (node (ref "C81") (pin "2") (pinfunction "2_2") (pintype "passive"))
      (node (ref "U13") (pin "G1") (pinfunction "VSSA_G1") (pintype "power_in"))
    )
    (net (code "69") (name "GND") (class "Default")
      (node (ref "C62") (pin "2") (pinfunction "2_2") (pintype "passive"))
      (node (ref "C63") (pin "2") (pinfunction "2_2") (pintype "passive"))
      (node (ref "C64") (pin "2") (pinfunction "2_2") (pintype "passive"))
      (node (ref "C65") (pin "2") (pinfunction "2_2") (pintype "passive"))
      (node (ref "C66") (pin "2") (pinfunction "2_2") (pintype "passive"))
      (node (ref "C67") (pin "2") (pinfunction "2_2") (pintype "passive"))
      (node (ref "C68") (pin "2") (pinfunction "2_2") (pintype "passive"))
      (node (ref "C69") (pin "2") (pinfunction "2_2") (pintype "passive"))
      (node (ref "C70") (pin "1") (pinfunction "1_1") (pintype "passive"))
      (node (ref "C71") (pin "1") (pinfunction "1_1") (pintype "passive"))
      (node (ref "C72") (pin "1") (pinfunction "1_1") (pintype "passive"))
      (node (ref "C73") (pin "1") (pinfunction "1_1") (pintype "passive"))
      (node (ref "C74") (pin "1") (pinfunction "1_1") (pintype "passive"))
      (node (ref "C75") (pin "1") (pinfunction "1_1") (pintype "passive"))
      (node (ref "C76") (pin "1") (pinfunction "1_1") (pintype "passive"))
      (node (ref "C77") (pin "1") (pinfunction "1_1") (pintype "passive"))
      (node (ref "C78") (pin "1") (pinfunction "1_1") (pintype "passive"))
      (node (ref "R39") (pin "1") (pinfunction "1_1") (pintype "passive"))
      (node (ref "U13") (pin "C2") (pinfunction "VSS_C2") (pintype "power_in"))
      (node (ref "U13") (pin "E4") (pinfunction "VSS_E4") (pintype "power_in"))
      (node (ref "U13") (pin "E5") (pinfunction "VSS_E5") (pintype "power_in"))
      (node (ref "U13") (pin "E6") (pinfunction "VSS_E6") (pintype "power_in"))
      (node (ref "U13") (pin "J1") (pinfunction "VSS_J1") (pintype "power_in"))
      (node (ref "Z2") (pin "2") (pinfunction "2_2") (pintype "passive"))
      (node (ref "Z2") (pin "4") (pinfunction "4_4") (pintype "passive"))
      (node (ref "uSD1") (pin "10") (pinfunction "WP_10") (pintype "passive"))
      (node (ref "uSD1") (pin "11") (pinfunction "GND_11") (pintype "passive"))
      (node (ref "uSD1") (pin "12") (pinfunction "GND_12") (pintype "passive"))
      (node (ref "uSD1") (pin "6") (pinfunction "VSS2_6") (pintype "passive"))
      (node (ref "uSD1") (pin "9") (pintype "passive"))
    )
    (net (code "70") (name "Net-(C66-Pad1)") (class "Default")
      (node (ref "C66") (pin "1") (pinfunction "1_1") (pintype "passive"))
      (node (ref "R40") (pin "1") (pinfunction "1_1") (pintype "passive"))
      (node (ref "Z2") (pin "1") (pinfunction "1_1") (pintype "passive"))
    )
    (net (code "71") (name "Net-(C67-Pad1)") (class "Default")
      (node (ref "C67") (pin "1") (pinfunction "1_1") (pintype "passive"))
      (node (ref "C68") (pin "1") (pinfunction "1_1") (pintype "passive"))
      (node (ref "U13") (pin "E7") (pinfunction "VCAP_E7") (pintype "power_in"))
      (node (ref "U13") (pin "F8") (pinfunction "VCAP_F8") (pintype "power_in"))
    )
    (net (code "72") (name "Net-(U13-BOOT0_{slash}_VPP)") (class "Default")
      (node (ref "J1") (pin "1") (pinfunction "1_1") (pintype "passive"))
      (node (ref "R39") (pin "2") (pinfunction "2_2") (pintype "passive"))
      (node (ref "U13") (pin "D5") (pinfunction "BOOT0_/_VPP_D5") (pintype "input"))
    )
    (net (code "73") (name "Net-(U13-PC14_{slash}_OSC32_IN_{slash}_OSC32_IN)") (class "Default")
      (node (ref "C63") (pin "1") (pinfunction "1_1") (pintype "passive"))
      (node (ref "U13") (pin "A1") (pinfunction "PC14_/_OSC32_IN_/_OSC32_IN_A1") (pintype "bidirectional"))
      (node (ref "Z1") (pin "2") (pinfunction "2_2") (pintype "passive"))
    )
    (net (code "74") (name "Net-(U13-PC15_{slash}_OSC32_OUT_{slash}_OSC32_OUT)") (class "Default")
      (node (ref "C64") (pin "1") (pinfunction "1_1") (pintype "passive"))
      (node (ref "U13") (pin "B1") (pinfunction "PC15_/_OSC32_OUT_/_OSC32_OUT_B1") (pintype "bidirectional"))
      (node (ref "Z1") (pin "1") (pinfunction "1_1") (pintype "passive"))
    )
    (net (code "75") (name "Net-(U13-PDR_ON)") (class "Default")
      (node (ref "R41") (pin "2") (pinfunction "2_2") (pintype "passive"))
      (node (ref "U13") (pin "F7") (pinfunction "PDR_ON_F7") (pintype "input"))
    )
    (net (code "76") (name "VREF_1.65V") (class "Default")
      (node (ref "U13") (pin "G2") (pinfunction "PA0_/_ADC1_INP16/WKUP0_/_TIM2_CH1/TIM2_ETR_/_TIM5_CH1_/_TIM8_ETR_/_TIM15_BKIN_/_USART2_CTS/USART2_NSS_/_UART4_TX_/_SDMMC2_CMD_/_SAI2_SD_B_/_ETH_MII_CRS_/_ADC1_INP16_/_WKUP0_G2") (pintype "bidirectional"))
    )
    (net (code "77") (name "unconnected-(U13-PB2_{slash}_COMP1_INP_{slash}_RTC_OUT_{slash}_SAI1_D1_{slash}_DFSDM1_CKIN1_{slash}_SAI1_SD_A_{slash}_SPI3_MOSI{slash}I2S3_SDO_{slash}_SAI4_SD_A_{slash}_QUADSPI_CLK_{slash}_SAI4_D1_{slash}_COMP1_INP-PadG5)") (class "Default")
      (node (ref "U13") (pin "G5") (pinfunction "PB2_/_COMP1_INP_/_RTC_OUT_/_SAI1_D1_/_DFSDM1_CKIN1_/_SAI1_SD_A_/_SPI3_MOSI/I2S3_SDO_/_SAI4_SD_A_/_QUADSPI_CLK_/_SAI4_D1_/_COMP1_INP_G5") (pintype "bidirectional"))
    )
    (net (code "78") (name "unconnected-(U13-PB4_{slash}_NJTRST_{slash}_TIM16_BKIN_{slash}_TIM3_CH1_{slash}_HRTIM_EEV6_{slash}_SPI1_MISO{slash}I2S1_SDI_{slash}_SPI3_MISO{slash}I2S3_SDI_{slash}_SPI2_NSS{slash}I2S2_WS_{slash}_SPI6_MISO_{slash}_SDMMC2_D3_{slash}_UART7_TX-PadA6)") (class "Default")
      (node (ref "U13") (pin "A6") (pinfunction "PB4_/_NJTRST_/_TIM16_BKIN_/_TIM3_CH1_/_HRTIM_EEV6_/_SPI1_MISO/I2S1_SDI_/_SPI3_MISO/I2S3_SDI_/_SPI2_NSS/I2S2_WS_/_SPI6_MISO_/_SDMMC2_D3_/_UART7_TX_A6") (pintype "bidirectional"))
    )
    (net (code "79") (name "unconnected-(U13-PB6_{slash}_TIM16_CH1N_{slash}_TIM4_CH1_{slash}_HRTIM_EEV8_{slash}_I2C1_SCL_{slash}_CEC_{slash}_I2C4_SCL_{slash}_USART1_TX_{slash}_LPUART1_TX_{slash}_FDCAN2_TX_{slash}_QUADSPI_BK1_NCS_{slash}_DFSDM1_DATIN5_{slash}_FMC_SDNE1_{slash}_DCMI_D5_{slash}_UART5_TX-PadB5)") (class "Default")
      (node (ref "U13") (pin "B5") (pinfunction "PB6_/_TIM16_CH1N_/_TIM4_CH1_/_HRTIM_EEV8_/_I2C1_SCL_/_CEC_/_I2C4_SCL_/_USART1_TX_/_LPUART1_TX_/_FDCAN2_TX_/_QUADSPI_BK1_NCS_/_DFSDM1_DATIN5_/_FMC_SDNE1_/_DCMI_D5_/_UART5_TX_B5") (pintype "bidirectional"))
    )
    (net (code "80") (name "unconnected-(U13-PB7_{slash}_PVD_IN_{slash}_TIM17_CH1N_{slash}_TIM4_CH2_{slash}_HRTIM_EEV9_{slash}_I2C1_SDA_{slash}_I2C4_SDA_{slash}_USART1_RX_{slash}_LPUART1_RX_{slash}_FDCAN2_TXFD_MODE_{slash}_DFSDM1_CKIN5_{slash}_FMC_NL_{slash}_DCMI_VSYNC_{slash}_PVD_IN-PadA5)") (class "Default")
      (node (ref "U13") (pin "A5") (pinfunction "PB7_/_PVD_IN_/_TIM17_CH1N_/_TIM4_CH2_/_HRTIM_EEV9_/_I2C1_SDA_/_I2C4_SDA_/_USART1_RX_/_LPUART1_RX_/_FDCAN2_TXFD_MODE_/_DFSDM1_CKIN5_/_FMC_NL_/_DCMI_VSYNC_/_PVD_IN_A5") (pintype "bidirectional"))
    )
    (net (code "81") (name "unconnected-(U13-PB11_{slash}_TIM2_CH4_{slash}_HRTIM_SCIN_{slash}_LPTIM2_ETR_{slash}_I2C2_SDA_{slash}_DFSDM1_CKIN7_{slash}_USART3_RX_{slash}_OTG_HS_ULPI_D4_{slash}_ETH_MII_TX_EN{slash}ETH_RMII_TX_EN_{slash}_LCD_G5-PadK7)") (class "Default")
      (node (ref "U13") (pin "K7") (pinfunction "PB11_/_TIM2_CH4_/_HRTIM_SCIN_/_LPTIM2_ETR_/_I2C2_SDA_/_DFSDM1_CKIN7_/_USART3_RX_/_OTG_HS_ULPI_D4_/_ETH_MII_TX_EN/ETH_RMII_TX_EN_/_LCD_G5_K7") (pintype "bidirectional"))
    )
    (net (code "82") (name "unconnected-(U13-PB12_{slash}_TIM1_BKIN_{slash}_I2C2_SMBA_{slash}_SPI2_NSS{slash}I2S2_WS_{slash}_DFSDM1_DATIN1_{slash}_USART3_CK_{slash}_FDCAN2_RX_{slash}_OTG_HS_ULPI_D5_{slash}_ETH_MII_TXD0{slash}ETH_RMII_TXD0_{slash}_OTG_HS_ID_{slash}_TIM1_BKIN_COMP12_{slash}_UART5_RX-PadK8)") (class "Default")
      (node (ref "U13") (pin "K8") (pinfunction "PB12_/_TIM1_BKIN_/_I2C2_SMBA_/_SPI2_NSS/I2S2_WS_/_DFSDM1_DATIN1_/_USART3_CK_/_FDCAN2_RX_/_OTG_HS_ULPI_D5_/_ETH_MII_TXD0/ETH_RMII_TXD0_/_OTG_HS_ID_/_TIM1_BKIN_COMP12_/_UART5_RX_K8") (pintype "bidirectional"))
    )
    (net (code "83") (name "unconnected-(U13-PC1_{slash}_ADC123_INN10{slash}ADC123_INP11{slash}RTC_TAMP3{slash}WKUP5_{slash}_TRACED0_{slash}_SAI1_D1_{slash}_DFSDM1_DATIN0_{slash}_DFSDM1_CKIN4_{slash}_SPI2_MOSI{slash}I2S2_SDO_{slash}_SAI1_SD_A_{slash}_SAI4_SD_A_{slash}_SDMMC2_CK_{slash}_SAI4_D1_{slash}_ETH_MDC_{slash}_MDIOS_MDC_{slash}_ADC123_INN10_{slash}_ADC123_INP11_{slash}_RTC_TAMP3{slash}WKUP5-PadF2)") (class "Default")
      (node (ref "U13") (pin "F2") (pinfunction "PC1_/_ADC123_INN10/ADC123_INP11/RTC_TAMP3/WKUP5_/_TRACED0_/_SAI1_D1_/_DFSDM1_DATIN0_/_DFSDM1_CKIN4_/_SPI2_MOSI/I2S2_SDO_/_SAI1_SD_A_/_SAI4_SD_A_/_SDMMC2_CK_/_SAI4_D1_/_ETH_MDC_/_MDIOS_MDC_/_ADC123_INN10_/_ADC123_INP11_/_RTC_TAMP3/WKUP5_F2") (pintype "bidirectional"))
    )
    (net (code "84") (name "unconnected-(U13-PD3_{slash}_DFSDM1_CKOUT_{slash}_SPI2_SCK{slash}I2S2_CK_{slash}_USART2_CTS{slash}USART2_NSS_{slash}_FMC_CLK_{slash}_DCMI_D5_{slash}_LCD_G7-PadC7)") (class "Default")
      (node (ref "U13") (pin "C7") (pinfunction "PD3_/_DFSDM1_CKOUT_/_SPI2_SCK/I2S2_CK_/_USART2_CTS/USART2_NSS_/_FMC_CLK_/_DCMI_D5_/_LCD_G7_C7") (pintype "bidirectional"))
    )
    (net (code "85") (name "unconnected-(U13-PD5_{slash}_HRTIM_EEV3_{slash}_USART2_TX_{slash}_FDCAN1_TXFD_MODE_{slash}_FMC_NWE-PadB6)") (class "Default")
      (node (ref "U13") (pin "B6") (pinfunction "PD5_/_HRTIM_EEV3_/_USART2_TX_/_FDCAN1_TXFD_MODE_/_FMC_NWE_B6") (pintype "bidirectional"))
    )
    (net (code "86") (name "unconnected-(U13-PD7_{slash}_DFSDM1_DATIN4_{slash}_SPI1_MOSI{slash}I2S1_SDO_{slash}_DFSDM1_CKIN1_{slash}_USART2_CK_{slash}_SPDIFRX1_IN1_{slash}_SDMMC2_CMD_{slash}_FMC_NE1-PadD6)") (class "Default")
      (node (ref "U13") (pin "D6") (pinfunction "PD7_/_DFSDM1_DATIN4_/_SPI1_MOSI/I2S1_SDO_/_DFSDM1_CKIN1_/_USART2_CK_/_SPDIFRX1_IN1_/_SDMMC2_CMD_/_FMC_NE1_D6") (pintype "bidirectional"))
    )
    (net (code "87") (name "unconnected-(U13-PD8_{slash}_DFSDM1_CKIN3_{slash}_SAI3_SCK_B_{slash}_USART3_TX_{slash}_SPDIFRX1_IN2_{slash}_FMC_D13{slash}FMC_DA13-PadK9)") (class "Default")
      (node (ref "U13") (pin "K9") (pinfunction "PD8_/_DFSDM1_CKIN3_/_SAI3_SCK_B_/_USART3_TX_/_SPDIFRX1_IN2_/_FMC_D13/FMC_DA13_K9") (pintype "bidirectional"))
    )
    (net (code "88") (name "unconnected-(U13-PD9_{slash}_DFSDM1_DATIN3_{slash}_SAI3_SD_B_{slash}_USART3_RX_{slash}_FDCAN2_RXFD_MODE_{slash}_FMC_D14{slash}FMC_DA14-PadJ9)") (class "Default")
      (node (ref "U13") (pin "J9") (pinfunction "PD9_/_DFSDM1_DATIN3_/_SAI3_SD_B_/_USART3_RX_/_FDCAN2_RXFD_MODE_/_FMC_D14/FMC_DA14_J9") (pintype "bidirectional"))
    )
    (net (code "89") (name "unconnected-(U13-PD10_{slash}_DFSDM1_CKOUT_{slash}_SAI3_FS_B_{slash}_USART3_CK_{slash}_FDCAN2_TXFD_MODE_{slash}_FMC_D15{slash}FMC_DA15_{slash}_LCD_B3-PadH9)") (class "Default")
      (node (ref "U13") (pin "H9") (pinfunction "PD10_/_DFSDM1_CKOUT_/_SAI3_FS_B_/_USART3_CK_/_FDCAN2_TXFD_MODE_/_FMC_D15/FMC_DA15_/_LCD_B3_H9") (pintype "bidirectional"))
    )
    (net (code "90") (name "unconnected-(U13-PD12_{slash}_LPTIM1_IN1_{slash}_TIM4_CH1_{slash}_LPTIM2_IN1_{slash}_I2C4_SCL_{slash}_USART3_RTS{slash}USART3_DE_{slash}_QUADSPI_BK1_IO1_{slash}_SAI2_FS_A_{slash}_FMC_A17-PadK10)") (class "Default")
      (node (ref "U13") (pin "K10") (pinfunction "PD12_/_LPTIM1_IN1_/_TIM4_CH1_/_LPTIM2_IN1_/_I2C4_SCL_/_USART3_RTS/USART3_DE_/_QUADSPI_BK1_IO1_/_SAI2_FS_A_/_FMC_A17_K10") (pintype "bidirectional"))
    )
    (net (code "91") (name "unconnected-(U13-PE5_{slash}_TRACED2_{slash}_SAI1_CK2_{slash}_DFSDM1_CKIN3_{slash}_TIM15_CH1_{slash}_SPI4_MISO_{slash}_SAI1_SCK_A_{slash}_SAI4_SCK_A_{slash}_SAI4_CK2_{slash}_FMC_A21_{slash}_DCMI_D6_{slash}_LCD_G0-PadD3)") (class "Default")
      (node (ref "U13") (pin "D3") (pinfunction "PE5_/_TRACED2_/_SAI1_CK2_/_DFSDM1_CKIN3_/_TIM15_CH1_/_SPI4_MISO_/_SAI1_SCK_A_/_SAI4_SCK_A_/_SAI4_CK2_/_FMC_A21_/_DCMI_D6_/_LCD_G0_D3") (pintype "bidirectional"))
    )
    (net (code "92") (name "unconnected-(U13-PE10_{slash}_COMP2_INM_{slash}_TIM1_CH2N_{slash}_DFSDM1_DATIN4_{slash}_UART7_CTS_{slash}_QUADSPI_BK2_IO3_{slash}_FMC_D7{slash}FMC_DA7_{slash}_COMP2_INM-PadG6)") (class "Default")
      (node (ref "U13") (pin "G6") (pinfunction "PE10_/_COMP2_INM_/_TIM1_CH2N_/_DFSDM1_DATIN4_/_UART7_CTS_/_QUADSPI_BK2_IO3_/_FMC_D7/FMC_DA7_/_COMP2_INM_G6") (pintype "bidirectional"))
    )
  )
)
